# Adafruit_AD849x_Thermo.net
KiCad netlist of a schematic drawn in EAGLE
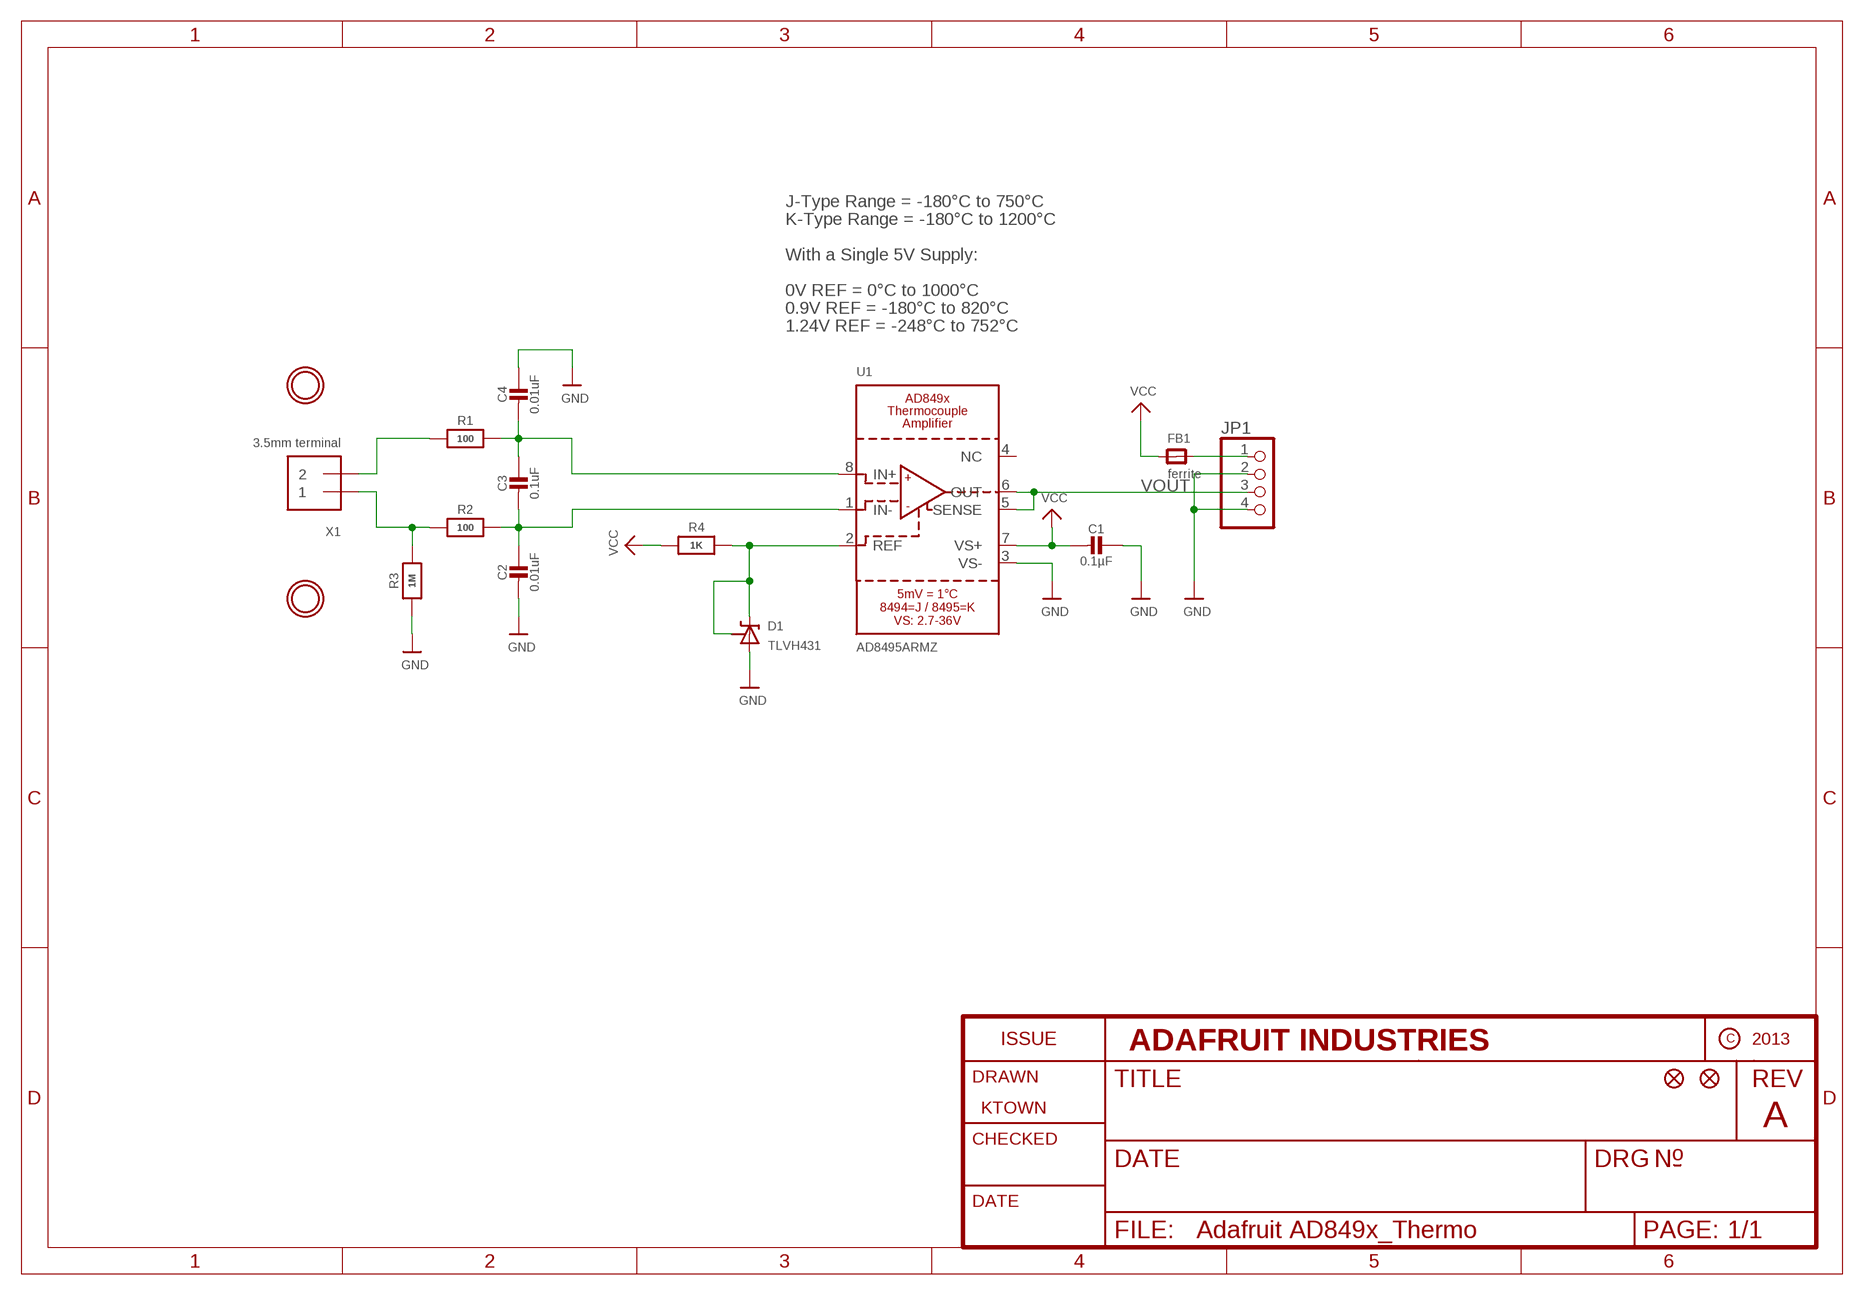
[diagram p0: schematic, sheet 1]

(export (version "E")
  (design (tool "Eeschema 10.0.6"))
  (components
    (comp (ref "C1")
      (value "0.1µF")
      (footprint "eagle-import:0805-NO")
      (libsource (lib "eagle-import") (part "CAP_CERAMIC0805-NOOUTLINE"))
    )
    (comp (ref "C2")
      (value "0.01uF")
      (footprint "eagle-import:0805-NO")
      (libsource (lib "eagle-import") (part "CAP_CERAMIC0805-NOOUTLINE"))
    )
    (comp (ref "C3")
      (value "0.1uF")
      (footprint "eagle-import:0805-NO")
      (libsource (lib "eagle-import") (part "CAP_CERAMIC0805-NOOUTLINE"))
    )
    (comp (ref "C4")
      (value "0.01uF")
      (footprint "eagle-import:0805-NO")
      (libsource (lib "eagle-import") (part "CAP_CERAMIC0805-NOOUTLINE"))
    )
    (comp (ref "D1")
      (value "TLVH431")
      (footprint "eagle-import:SOT23-R")
      (libsource (lib "eagle-import") (part "SHUNT-VREF"))
    )
    (comp (ref "FB1")
      (value "ferrite")
      (footprint "eagle-import:0805")
      (libsource (lib "eagle-import") (part "FERRITE0805"))
    )
    (comp (ref "FID1")
      (value "FIDUCIAL\"\"")
      (footprint "eagle-import:FIDUCIAL_1MM")
      (libsource (lib "eagle-import") (part "FIDUCIAL{dblquote}{dblquote}"))
    )
    (comp (ref "FID2")
      (value "FIDUCIAL\"\"")
      (footprint "eagle-import:FIDUCIAL_1MM")
      (libsource (lib "eagle-import") (part "FIDUCIAL{dblquote}{dblquote}"))
    )
    (comp (ref "JP1")
      (value "HEADER-1X4ROUND")
      (footprint "eagle-import:1X04_ROUND")
      (libsource (lib "eagle-import") (part "HEADER-1X4ROUND"))
    )
    (comp (ref "R1")
      (value "100")
      (footprint "eagle-import:0805-NO")
      (libsource (lib "eagle-import") (part "RESISTOR0805_NOOUTLINE"))
    )
    (comp (ref "R2")
      (value "100")
      (footprint "eagle-import:0805-NO")
      (libsource (lib "eagle-import") (part "RESISTOR0805_NOOUTLINE"))
    )
    (comp (ref "R3")
      (value "1M")
      (footprint "eagle-import:0805-NO")
      (libsource (lib "eagle-import") (part "RESISTOR0805_NOOUTLINE"))
    )
    (comp (ref "R4")
      (value "1K")
      (footprint "eagle-import:0805-NO")
      (libsource (lib "eagle-import") (part "RESISTOR0805_NOOUTLINE"))
    )
    (comp (ref "U$11")
      (value "MOUNTINGHOLE2.5")
      (footprint "eagle-import:MOUNTINGHOLE_2.5_PLATED")
      (libsource (lib "eagle-import") (part "MOUNTINGHOLE2.5"))
    )
    (comp (ref "U$12")
      (value "MOUNTINGHOLE2.5")
      (footprint "eagle-import:MOUNTINGHOLE_2.5_PLATED")
      (libsource (lib "eagle-import") (part "MOUNTINGHOLE2.5"))
    )
    (comp (ref "U1")
      (value "AD8495ARMZ")
      (footprint "eagle-import:MSOP8_0.65MM")
      (libsource (lib "eagle-import") (part "AD849X"))
    )
    (comp (ref "X1")
      (value "3.5mm terminal")
      (footprint "eagle-import:TERMBLOCK_1X2-3.5MM")
      (libsource (lib "eagle-import") (part "TERMBLOCK_1X2"))
    )
  )
  (nets
    (net (code "1") (name "/VOUT") (class "Default")
      (node (ref "JP1") (pin "3") (pinfunction "3_3") (pintype "passive"))
      (node (ref "U1") (pin "5") (pinfunction "SENSE_5") (pintype "bidirectional"))
      (node (ref "U1") (pin "6") (pinfunction "OUT_6") (pintype "output"))
    )
    (net (code "2") (name "GND") (class "Default")
      (node (ref "C1") (pin "1") (pinfunction "1_1") (pintype "passive"))
      (node (ref "C2") (pin "2") (pinfunction "2_2") (pintype "passive"))
      (node (ref "C4") (pin "1") (pinfunction "1_1") (pintype "passive"))
      (node (ref "D1") (pin "3") (pinfunction "A_3") (pintype "passive"))
      (node (ref "JP1") (pin "2") (pinfunction "2_2") (pintype "passive"))
      (node (ref "JP1") (pin "4") (pinfunction "4_4") (pintype "passive"))
      (node (ref "R3") (pin "1") (pinfunction "1_1") (pintype "passive"))
      (node (ref "U1") (pin "3") (pinfunction "VS-_3") (pintype "power_in"))
    )
    (net (code "3") (name "Net-(D1-C)") (class "Default")
      (node (ref "D1") (pin "1") (pinfunction "VREF_1") (pintype "passive"))
      (node (ref "D1") (pin "2") (pinfunction "C_2") (pintype "passive"))
      (node (ref "R4") (pin "2") (pinfunction "2_2") (pintype "passive"))
      (node (ref "U1") (pin "2") (pinfunction "REF_2") (pintype "input"))
    )
    (net (code "4") (name "Net-(FB1-P$2)") (class "Default")
      (node (ref "FB1") (pin "2") (pinfunction "P$2_2") (pintype "passive"))
      (node (ref "JP1") (pin "1") (pinfunction "1_1") (pintype "passive"))
    )
    (net (code "5") (name "Net-(R1-Pad1)") (class "Default")
      (node (ref "R1") (pin "1") (pinfunction "1_1") (pintype "passive"))
      (node (ref "X1") (pin "2") (pinfunction "2_2") (pintype "passive"))
    )
    (net (code "6") (name "Net-(R2-Pad1)") (class "Default")
      (node (ref "R2") (pin "1") (pinfunction "1_1") (pintype "passive"))
      (node (ref "R3") (pin "2") (pinfunction "2_2") (pintype "passive"))
      (node (ref "X1") (pin "1") (pinfunction "1_1") (pintype "passive"))
    )
    (net (code "7") (name "Net-(U1-IN+)") (class "Default")
      (node (ref "C3") (pin "1") (pinfunction "1_1") (pintype "passive"))
      (node (ref "C4") (pin "2") (pinfunction "2_2") (pintype "passive"))
      (node (ref "R1") (pin "2") (pinfunction "2_2") (pintype "passive"))
      (node (ref "U1") (pin "8") (pinfunction "IN+_8") (pintype "input"))
    )
    (net (code "8") (name "Net-(U1-IN-)") (class "Default")
      (node (ref "C2") (pin "1") (pinfunction "1_1") (pintype "passive"))
      (node (ref "C3") (pin "2") (pinfunction "2_2") (pintype "passive"))
      (node (ref "R2") (pin "2") (pinfunction "2_2") (pintype "passive"))
      (node (ref "U1") (pin "1") (pinfunction "IN-_1") (pintype "input"))
    )
    (net (code "9") (name "VCC") (class "Default")
      (node (ref "C1") (pin "2") (pinfunction "2_2") (pintype "passive"))
      (node (ref "FB1") (pin "1") (pinfunction "P$1_1") (pintype "passive"))
      (node (ref "R4") (pin "1") (pinfunction "1_1") (pintype "passive"))
      (node (ref "U1") (pin "7") (pinfunction "VS+_7") (pintype "power_in"))
    )
    (net (code "10") (name "unconnected-(U1-NC-Pad4)") (class "Default")
      (node (ref "U1") (pin "4") (pinfunction "NC_4") (pintype "no_connect"))
    )
  )
)
